# TX_LPF_Add_on.net
KiCad netlist of a schematic drawn in Altium Designer
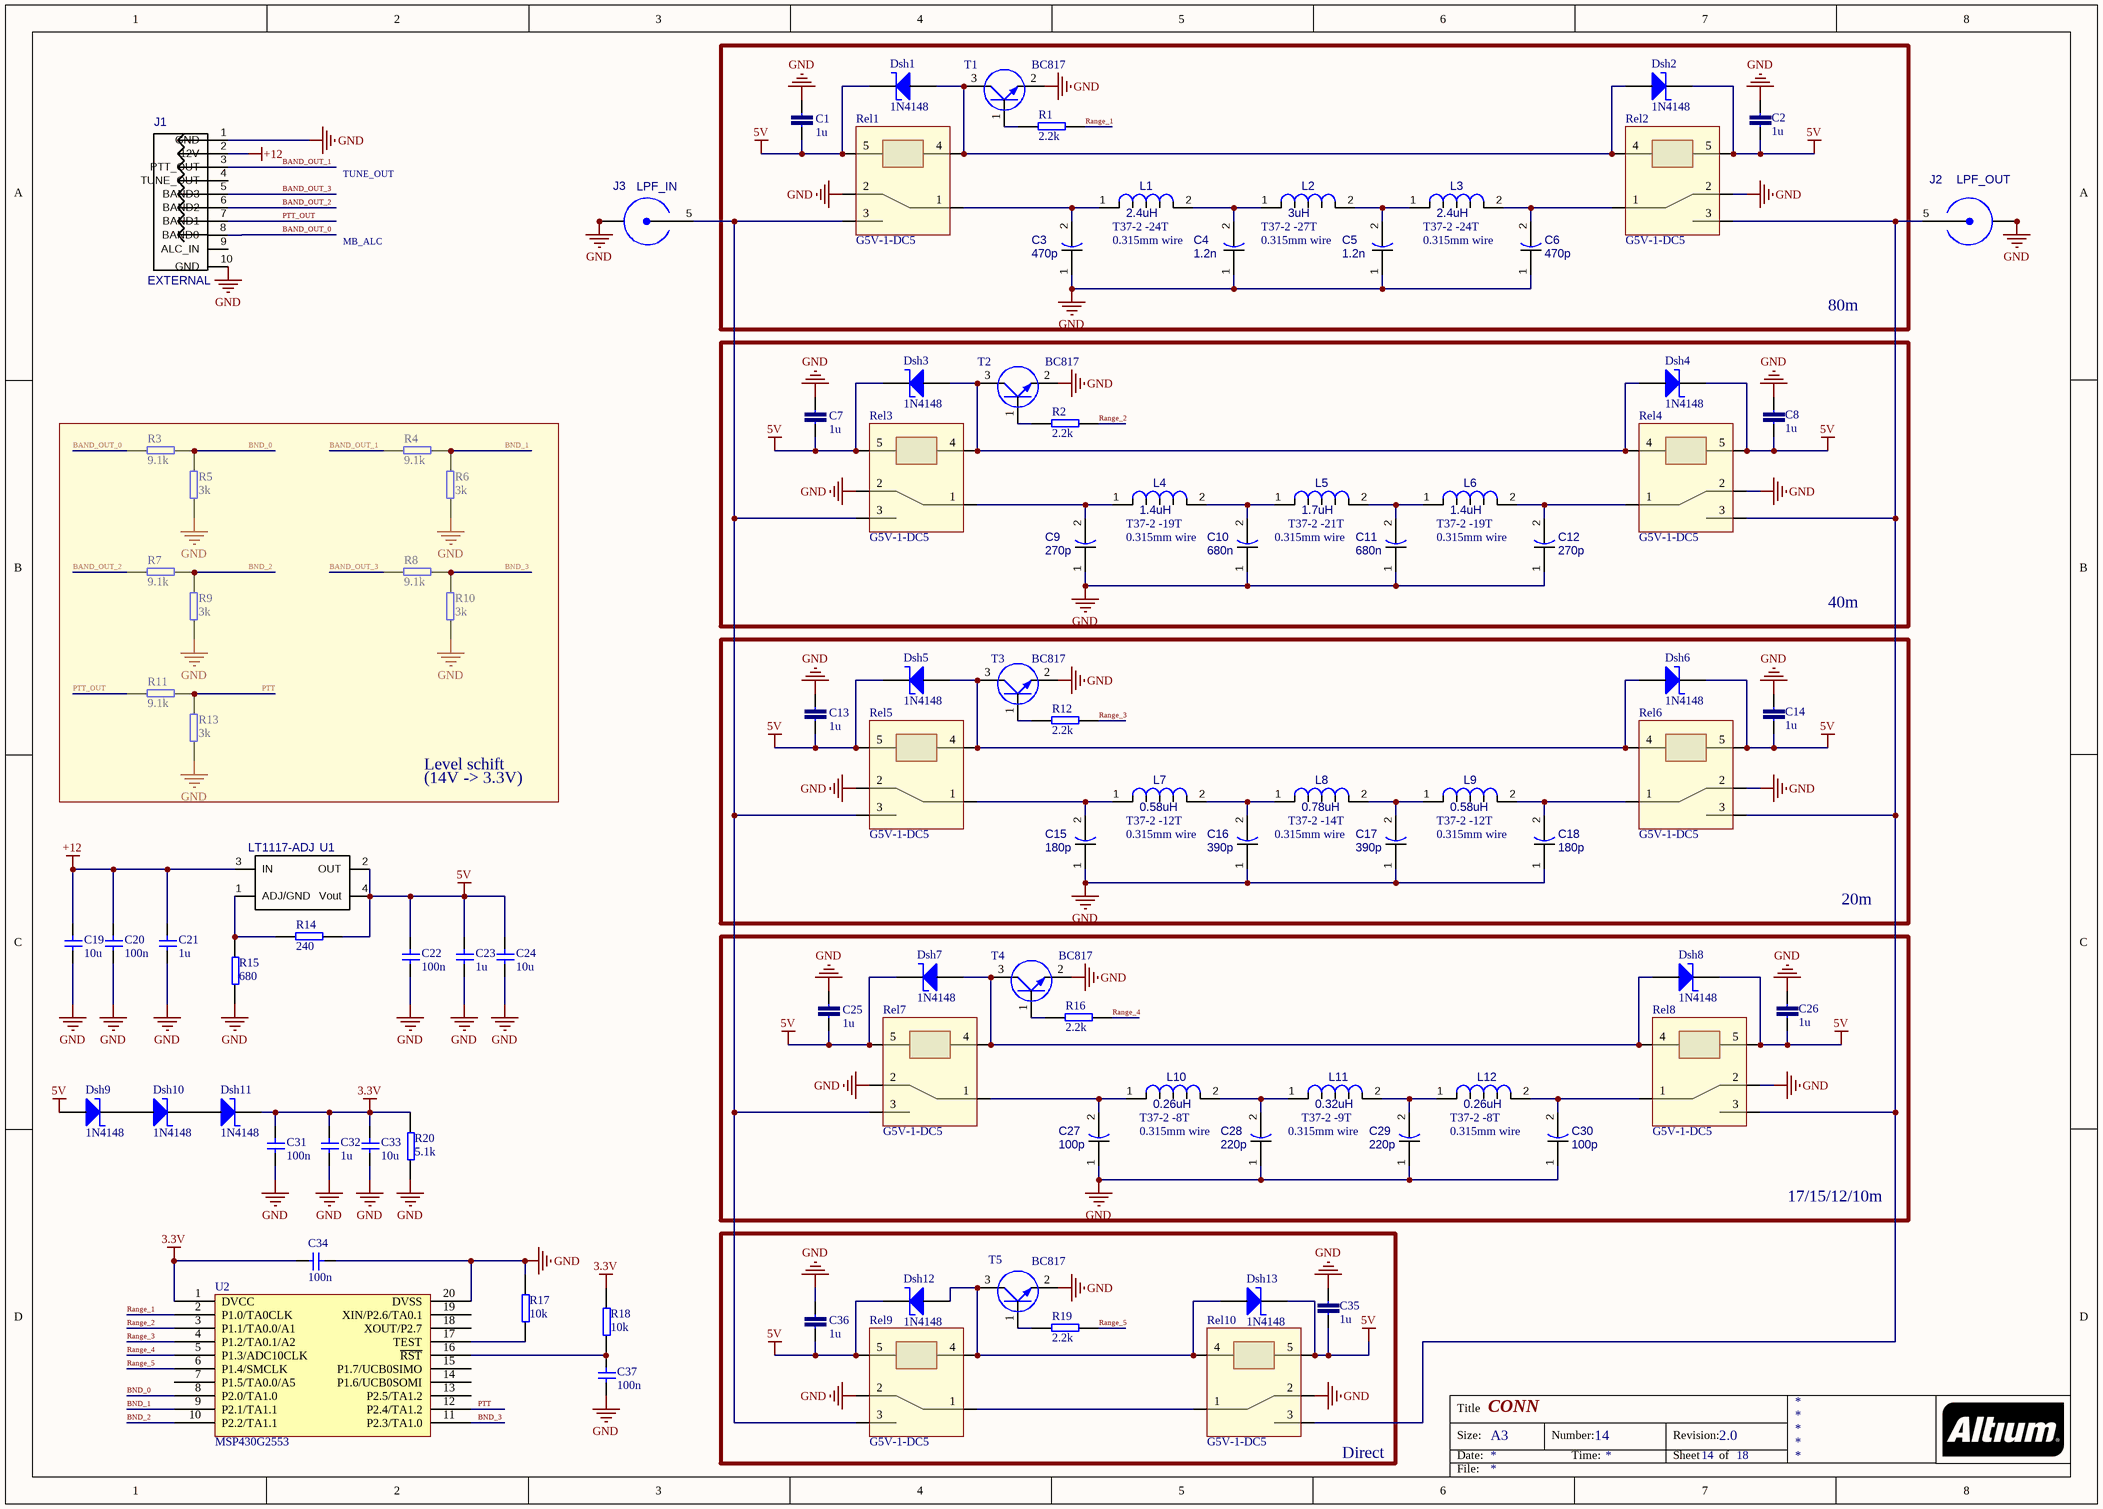
[diagram p0: TX_LPF_Add_on.SchDoc]

(export (version "E")
  (design (tool "Eeschema 10.0.6"))
  (components
    (comp (ref "C1")
      (value "1u")
      (footprint "0805S")
      (description "Capacitor")
      (libsource (lib "") (part "C-EUC0805_1"))
    )
    (comp (ref "C2")
      (value "1u")
      (footprint "0805S")
      (description "Capacitor")
      (libsource (lib "XXYZZB_1") (part "C-EUC0805"))
    )
    (comp (ref "C3")
      (value "470p")
      (footprint "CAP_5mm")
      (description "CAP_1206")
      (fields (field (name "Comment") "CAP_5mm"))
      (libsource (lib "RF-UNIT") (part "CAP_5mm"))
    )
    (comp (ref "C4")
      (value "1.2n")
      (footprint "CAP_5mm")
      (description "CAP_1206")
      (fields (field (name "Comment") "CAP_5mm"))
      (libsource (lib "RF-UNIT") (part "CAP_5mm"))
    )
    (comp (ref "C5")
      (value "1.2n")
      (footprint "CAP_5mm")
      (description "CAP_1206")
      (fields (field (name "Comment") "CAP_5mm"))
      (libsource (lib "RF-UNIT") (part "CAP_5mm"))
    )
    (comp (ref "C6")
      (value "470p")
      (footprint "CAP_5mm")
      (description "CAP_1206")
      (fields (field (name "Comment") "CAP_5mm"))
      (libsource (lib "RF-UNIT") (part "CAP_5mm"))
    )
    (comp (ref "C7")
      (value "1u")
      (footprint "0805S")
      (description "Capacitor")
      (libsource (lib "") (part "C-EUC0805_1"))
    )
    (comp (ref "C8")
      (value "1u")
      (footprint "0805S")
      (description "Capacitor")
      (libsource (lib "XXYZZB_1") (part "C-EUC0805"))
    )
    (comp (ref "C9")
      (value "270p")
      (footprint "CAP_5mm")
      (description "CAP_1206")
      (fields (field (name "Comment") "CAP_5mm"))
      (libsource (lib "RF-UNIT") (part "CAP_5mm"))
    )
    (comp (ref "C10")
      (value "680n")
      (footprint "CAP_5mm")
      (description "CAP_1206")
      (fields (field (name "Comment") "CAP_5mm"))
      (libsource (lib "RF-UNIT") (part "CAP_5mm"))
    )
    (comp (ref "C11")
      (value "680n")
      (footprint "CAP_5mm")
      (description "CAP_1206")
      (fields (field (name "Comment") "CAP_5mm"))
      (libsource (lib "RF-UNIT") (part "CAP_5mm"))
    )
    (comp (ref "C12")
      (value "270p")
      (footprint "CAP_5mm")
      (description "CAP_1206")
      (fields (field (name "Comment") "CAP_5mm"))
      (libsource (lib "RF-UNIT") (part "CAP_5mm"))
    )
    (comp (ref "C13")
      (value "1u")
      (footprint "0805S")
      (description "Capacitor")
      (libsource (lib "") (part "C-EUC0805_1"))
    )
    (comp (ref "C14")
      (value "1u")
      (footprint "0805S")
      (description "Capacitor")
      (libsource (lib "XXYZZB_1") (part "C-EUC0805"))
    )
    (comp (ref "C15")
      (value "180p")
      (footprint "CAP_5mm")
      (description "CAP_1206")
      (fields (field (name "Comment") "CAP_5mm"))
      (libsource (lib "RF-UNIT") (part "CAP_5mm"))
    )
    (comp (ref "C16")
      (value "390p")
      (footprint "CAP_5mm")
      (description "CAP_1206")
      (fields (field (name "Comment") "CAP_5mm"))
      (libsource (lib "RF-UNIT") (part "CAP_5mm"))
    )
    (comp (ref "C17")
      (value "390p")
      (footprint "CAP_5mm")
      (description "CAP_1206")
      (fields (field (name "Comment") "CAP_5mm"))
      (libsource (lib "RF-UNIT") (part "CAP_5mm"))
    )
    (comp (ref "C18")
      (value "180p")
      (footprint "CAP_5mm")
      (description "CAP_1206")
      (fields (field (name "Comment") "CAP_5mm"))
      (libsource (lib "RF-UNIT") (part "CAP_5mm"))
    )
    (comp (ref "C19")
      (value "10u")
      (footprint "CAP_1206")
      (description "Capacitor")
      (fields (field (name "Comment") "C0805"))
      (libsource (lib "Ivan DXP SCH LIB") (part "C0805"))
    )
    (comp (ref "C20")
      (value "100n")
      (footprint "0805S")
      (description "Capacitor")
      (fields (field (name "Comment") "C0805"))
      (libsource (lib "Ivan DXP SCH LIB") (part "C0805"))
    )
    (comp (ref "C21")
      (value "1u")
      (footprint "0805S")
      (description "Capacitor")
      (fields (field (name "Comment") "C0805"))
      (libsource (lib "Ivan DXP SCH LIB") (part "C0805"))
    )
    (comp (ref "C22")
      (value "100n")
      (footprint "0805S")
      (description "Capacitor")
      (fields (field (name "Comment") "C0805"))
      (libsource (lib "Ivan DXP SCH LIB") (part "C0805"))
    )
    (comp (ref "C23")
      (value "1u")
      (footprint "0805S")
      (description "Capacitor")
      (fields (field (name "Comment") "C0805"))
      (libsource (lib "Ivan DXP SCH LIB") (part "C0805"))
    )
    (comp (ref "C24")
      (value "10u")
      (footprint "CAP_1206")
      (description "Capacitor")
      (fields (field (name "Comment") "C0805"))
      (libsource (lib "Ivan DXP SCH LIB") (part "C0805"))
    )
    (comp (ref "C25")
      (value "1u")
      (footprint "0805S")
      (description "Capacitor")
      (libsource (lib "") (part "C-EUC0805_1"))
    )
    (comp (ref "C26")
      (value "1u")
      (footprint "0805S")
      (description "Capacitor")
      (libsource (lib "XXYZZB_1") (part "C-EUC0805"))
    )
    (comp (ref "C27")
      (value "100p")
      (footprint "CAP_5mm")
      (description "CAP_1206")
      (fields (field (name "Comment") "CAP_5mm"))
      (libsource (lib "RF-UNIT") (part "CAP_5mm"))
    )
    (comp (ref "C28")
      (value "220p")
      (footprint "CAP_5mm")
      (description "CAP_1206")
      (fields (field (name "Comment") "CAP_5mm"))
      (libsource (lib "RF-UNIT") (part "CAP_5mm"))
    )
    (comp (ref "C29")
      (value "220p")
      (footprint "CAP_5mm")
      (description "CAP_1206")
      (fields (field (name "Comment") "CAP_5mm"))
      (libsource (lib "RF-UNIT") (part "CAP_5mm"))
    )
    (comp (ref "C30")
      (value "100p")
      (footprint "CAP_5mm")
      (description "CAP_1206")
      (fields (field (name "Comment") "CAP_5mm"))
      (libsource (lib "RF-UNIT") (part "CAP_5mm"))
    )
    (comp (ref "C31")
      (value "100n")
      (footprint "0805S")
      (description "Capacitor")
      (fields (field (name "Comment") "C0805"))
      (libsource (lib "Ivan DXP SCH LIB") (part "C0805"))
    )
    (comp (ref "C32")
      (value "1u")
      (footprint "0805S")
      (description "Capacitor")
      (fields (field (name "Comment") "C0805"))
      (libsource (lib "Ivan DXP SCH LIB") (part "C0805"))
    )
    (comp (ref "C33")
      (value "10u")
      (footprint "CAP_1206")
      (description "Capacitor")
      (fields (field (name "Comment") "C0805"))
      (libsource (lib "Ivan DXP SCH LIB") (part "C0805"))
    )
    (comp (ref "C34")
      (value "100n")
      (footprint "0805S")
      (description "Capacitor")
      (fields (field (name "Comment") "C0805"))
      (libsource (lib "Ivan DXP SCH LIB") (part "C0805"))
    )
    (comp (ref "C35")
      (value "1u")
      (footprint "0805S")
      (description "Capacitor")
      (libsource (lib "XXYZZB_1") (part "C-EUC0805"))
    )
    (comp (ref "C36")
      (value "1u")
      (footprint "0805S")
      (description "Capacitor")
      (libsource (lib "") (part "C-EUC0805_1"))
    )
    (comp (ref "C37")
      (value "100n")
      (footprint "0805S")
      (description "Capacitor")
      (fields (field (name "Comment") "C0805"))
      (libsource (lib "Ivan DXP SCH LIB") (part "C0805"))
    )
    (comp (ref "Dsh1")
      (value "1N4148")
      (footprint "1N4148 (1005)")
      (description "Diode Shottky")
      (fields (field (name "Comment") "DIODE_Shottky_Micr.M"))
      (libsource (lib "Ivan DXP SCH LIB") (part "DIODE_Shottky_Micr.M"))
    )
    (comp (ref "Dsh2")
      (value "1N4148")
      (footprint "1N4148 (1005)")
      (description "Diode Shottky")
      (fields (field (name "Comment") "DIODE_Shottky_Micr.M"))
      (libsource (lib "Ivan DXP SCH LIB") (part "DIODE_Shottky_Micr.M"))
    )
    (comp (ref "Dsh3")
      (value "1N4148")
      (footprint "1N4148 (1005)")
      (description "Diode Shottky")
      (fields (field (name "Comment") "DIODE_Shottky_Micr.M"))
      (libsource (lib "Ivan DXP SCH LIB") (part "DIODE_Shottky_Micr.M"))
    )
    (comp (ref "Dsh4")
      (value "1N4148")
      (footprint "1N4148 (1005)")
      (description "Diode Shottky")
      (fields (field (name "Comment") "DIODE_Shottky_Micr.M"))
      (libsource (lib "Ivan DXP SCH LIB") (part "DIODE_Shottky_Micr.M"))
    )
    (comp (ref "Dsh5")
      (value "1N4148")
      (footprint "1N4148 (1005)")
      (description "Diode Shottky")
      (fields (field (name "Comment") "DIODE_Shottky_Micr.M"))
      (libsource (lib "Ivan DXP SCH LIB") (part "DIODE_Shottky_Micr.M"))
    )
    (comp (ref "Dsh6")
      (value "1N4148")
      (footprint "1N4148 (1005)")
      (description "Diode Shottky")
      (fields (field (name "Comment") "DIODE_Shottky_Micr.M"))
      (libsource (lib "Ivan DXP SCH LIB") (part "DIODE_Shottky_Micr.M"))
    )
    (comp (ref "Dsh7")
      (value "1N4148")
      (footprint "1N4148 (1005)")
      (description "Diode Shottky")
      (fields (field (name "Comment") "DIODE_Shottky_Micr.M"))
      (libsource (lib "Ivan DXP SCH LIB") (part "DIODE_Shottky_Micr.M"))
    )
    (comp (ref "Dsh8")
      (value "1N4148")
      (footprint "1N4148 (1005)")
      (description "Diode Shottky")
      (fields (field (name "Comment") "DIODE_Shottky_Micr.M"))
      (libsource (lib "Ivan DXP SCH LIB") (part "DIODE_Shottky_Micr.M"))
    )
    (comp (ref "Dsh9")
      (value "1N4148")
      (footprint "1N4148 (1005)")
      (description "Diode Shottky")
      (fields (field (name "Comment") "DIODE_Shottky_Micr.M"))
      (libsource (lib "Ivan DXP SCH LIB") (part "DIODE_Shottky_Micr.M"))
    )
    (comp (ref "Dsh10")
      (value "1N4148")
      (footprint "1N4148 (1005)")
      (description "Diode Shottky")
      (fields (field (name "Comment") "DIODE_Shottky_Micr.M"))
      (libsource (lib "Ivan DXP SCH LIB") (part "DIODE_Shottky_Micr.M"))
    )
    (comp (ref "Dsh11")
      (value "1N4148")
      (footprint "1N4148 (1005)")
      (description "Diode Shottky")
      (fields (field (name "Comment") "DIODE_Shottky_Micr.M"))
      (libsource (lib "Ivan DXP SCH LIB") (part "DIODE_Shottky_Micr.M"))
    )
    (comp (ref "Dsh12")
      (value "1N4148")
      (footprint "1N4148 (1005)")
      (description "Diode Shottky")
      (fields (field (name "Comment") "DIODE_Shottky_Micr.M"))
      (libsource (lib "Ivan DXP SCH LIB") (part "DIODE_Shottky_Micr.M"))
    )
    (comp (ref "Dsh13")
      (value "1N4148")
      (footprint "1N4148 (1005)")
      (description "Diode Shottky")
      (fields (field (name "Comment") "DIODE_Shottky_Micr.M"))
      (libsource (lib "Ivan DXP SCH LIB") (part "DIODE_Shottky_Micr.M"))
    )
    (comp (ref "J1")
      (value "EXTERNAL")
      (footprint "90131-0126")
      (description "2*5 PIN")
      (libsource (lib "RF-UNIT") (part "90131-0126"))
    )
    (comp (ref "J2")
      (value "LPF_OUT")
      (footprint "31-5431")
      (description "SMA")
      (fields (field (name "Comment") "Output"))
      (libsource (lib "RF-UNIT_1") (part "31-5431"))
    )
    (comp (ref "J3")
      (value "LPF_IN")
      (footprint "31-5431")
      (description "SMA")
      (fields (field (name "Comment") "Input"))
      (libsource (lib "RF-UNIT_1") (part "31-5431"))
    )
    (comp (ref "L1")
      (value "2.4uH")
      (footprint "IND_T37-2")
      (description "IND_T37-2")
      (libsource (lib "RF-UNIT") (part "IND_T37-2"))
    )
    (comp (ref "L2")
      (value "3uH")
      (footprint "IND_T37-2")
      (description "IND_T37-2")
      (libsource (lib "RF-UNIT") (part "IND_T37-2"))
    )
    (comp (ref "L3")
      (value "2.4uH")
      (footprint "IND_T37-2")
      (description "IND_T37-2")
      (libsource (lib "RF-UNIT") (part "IND_T37-2"))
    )
    (comp (ref "L4")
      (value "1.4uH")
      (footprint "IND_T37-2")
      (description "IND_T37-2")
      (libsource (lib "RF-UNIT") (part "IND_T37-2"))
    )
    (comp (ref "L5")
      (value "1.7uH")
      (footprint "IND_T37-2")
      (description "IND_T37-2")
      (libsource (lib "RF-UNIT") (part "IND_T37-2"))
    )
    (comp (ref "L6")
      (value "1.4uH")
      (footprint "IND_T37-2")
      (description "IND_T37-2")
      (libsource (lib "RF-UNIT") (part "IND_T37-2"))
    )
    (comp (ref "L7")
      (value "0.58uH")
      (footprint "IND_T37-2")
      (description "IND_T37-2")
      (libsource (lib "RF-UNIT") (part "IND_T37-2"))
    )
    (comp (ref "L8")
      (value "0.78uH")
      (footprint "IND_T37-2")
      (description "IND_T37-2")
      (libsource (lib "RF-UNIT") (part "IND_T37-2"))
    )
    (comp (ref "L9")
      (value "0.58uH")
      (footprint "IND_T37-2")
      (description "IND_T37-2")
      (libsource (lib "RF-UNIT") (part "IND_T37-2"))
    )
    (comp (ref "L10")
      (value "0.26uH")
      (footprint "IND_T37-2")
      (description "IND_T37-2")
      (libsource (lib "RF-UNIT") (part "IND_T37-2"))
    )
    (comp (ref "L11")
      (value "0.32uH")
      (footprint "IND_T37-2")
      (description "IND_T37-2")
      (libsource (lib "RF-UNIT") (part "IND_T37-2"))
    )
    (comp (ref "L12")
      (value "0.26uH")
      (footprint "IND_T37-2")
      (description "IND_T37-2")
      (libsource (lib "RF-UNIT") (part "IND_T37-2"))
    )
    (comp (ref "R1")
      (value "2.2k")
      (footprint "0805S")
      (description "Resistor")
      (libsource (lib "Ivan DXP SCH LIB") (part "R0805"))
    )
    (comp (ref "R2")
      (value "2.2k")
      (footprint "0805S")
      (description "Resistor")
      (libsource (lib "Ivan DXP SCH LIB") (part "R0805"))
    )
    (comp (ref "R3")
      (value "9.1k")
      (footprint "0805S")
      (description "Resistor")
      (fields (field (name "Comment") "R0805"))
      (libsource (lib "Ivan DXP SCH LIB") (part "R0805"))
    )
    (comp (ref "R4")
      (value "9.1k")
      (footprint "0805S")
      (description "Resistor")
      (fields (field (name "Comment") "R0805"))
      (libsource (lib "Ivan DXP SCH LIB") (part "R0805"))
    )
    (comp (ref "R5")
      (value "3k")
      (footprint "0805S")
      (description "Resistor")
      (fields (field (name "Comment") "R0805"))
      (libsource (lib "") (part "R0805_2"))
    )
    (comp (ref "R6")
      (value "3k")
      (footprint "0805S")
      (description "Resistor")
      (fields (field (name "Comment") "R0805"))
      (libsource (lib "") (part "R0805_2"))
    )
    (comp (ref "R7")
      (value "9.1k")
      (footprint "0805S")
      (description "Resistor")
      (fields (field (name "Comment") "R0805"))
      (libsource (lib "Ivan DXP SCH LIB") (part "R0805"))
    )
    (comp (ref "R8")
      (value "9.1k")
      (footprint "0805S")
      (description "Resistor")
      (fields (field (name "Comment") "R0805"))
      (libsource (lib "Ivan DXP SCH LIB") (part "R0805"))
    )
    (comp (ref "R9")
      (value "3k")
      (footprint "0805S")
      (description "Resistor")
      (fields (field (name "Comment") "R0805"))
      (libsource (lib "") (part "R0805_2"))
    )
    (comp (ref "R10")
      (value "3k")
      (footprint "0805S")
      (description "Resistor")
      (fields (field (name "Comment") "R0805"))
      (libsource (lib "") (part "R0805_2"))
    )
    (comp (ref "R11")
      (value "9.1k")
      (footprint "0805S")
      (description "Resistor")
      (fields (field (name "Comment") "R0805"))
      (libsource (lib "Ivan DXP SCH LIB") (part "R0805"))
    )
    (comp (ref "R12")
      (value "2.2k")
      (footprint "0805S")
      (description "Resistor")
      (libsource (lib "Ivan DXP SCH LIB") (part "R0805"))
    )
    (comp (ref "R13")
      (value "3k")
      (footprint "0805S")
      (description "Resistor")
      (fields (field (name "Comment") "R0805"))
      (libsource (lib "") (part "R0805_2"))
    )
    (comp (ref "R14")
      (value "240")
      (footprint "0805S")
      (description "Resistor")
      (fields (field (name "Comment") "R0805"))
      (libsource (lib "Ivan DXP SCH LIB") (part "R0805"))
    )
    (comp (ref "R15")
      (value "680")
      (footprint "0805S")
      (description "Resistor")
      (fields (field (name "Comment") "R0805"))
      (libsource (lib "") (part "R0805_1"))
    )
    (comp (ref "R16")
      (value "2.2k")
      (footprint "0805S")
      (description "Resistor")
      (libsource (lib "Ivan DXP SCH LIB") (part "R0805"))
    )
    (comp (ref "R17")
      (value "10k")
      (footprint "0805S")
      (description "Resistor")
      (fields (field (name "Comment") "R0805"))
      (libsource (lib "") (part "R0805_1"))
    )
    (comp (ref "R18")
      (value "10k")
      (footprint "0805S")
      (description "Resistor")
      (fields (field (name "Comment") "R0805"))
      (libsource (lib "") (part "R0805_1"))
    )
    (comp (ref "R19")
      (value "2.2k")
      (footprint "0805S")
      (description "Resistor")
      (libsource (lib "Ivan DXP SCH LIB") (part "R0805"))
    )
    (comp (ref "R20")
      (value "5.1k")
      (footprint "0805S")
      (description "Resistor")
      (fields (field (name "Comment") "R0805"))
      (libsource (lib "") (part "R0805_1"))
    )
    (comp (ref "Rel1")
      (value "G5V-1-DC5")
      (footprint "G5V-1")
      (libsource (lib "IC_Texas_Instruments_ADS805E_eec") (part "G5V-1-DC5"))
    )
    (comp (ref "Rel2") (value "G5V-1-DC5") (footprint "G5V-1") (libsource (lib "") (part "G5V-1-DC5_1")))
    (comp (ref "Rel3")
      (value "G5V-1-DC5")
      (footprint "G5V-1")
      (libsource (lib "IC_Texas_Instruments_ADS805E_eec") (part "G5V-1-DC5"))
    )
    (comp (ref "Rel4") (value "G5V-1-DC5") (footprint "G5V-1") (libsource (lib "") (part "G5V-1-DC5_1")))
    (comp (ref "Rel5")
      (value "G5V-1-DC5")
      (footprint "G5V-1")
      (libsource (lib "IC_Texas_Instruments_ADS805E_eec") (part "G5V-1-DC5"))
    )
    (comp (ref "Rel6") (value "G5V-1-DC5") (footprint "G5V-1") (libsource (lib "") (part "G5V-1-DC5_1")))
    (comp (ref "Rel7")
      (value "G5V-1-DC5")
      (footprint "G5V-1")
      (libsource (lib "IC_Texas_Instruments_ADS805E_eec") (part "G5V-1-DC5"))
    )
    (comp (ref "Rel8") (value "G5V-1-DC5") (footprint "G5V-1") (libsource (lib "") (part "G5V-1-DC5_1")))
    (comp (ref "Rel9")
      (value "G5V-1-DC5")
      (footprint "G5V-1")
      (libsource (lib "IC_Texas_Instruments_ADS805E_eec") (part "G5V-1-DC5"))
    )
    (comp (ref "Rel10") (value "G5V-1-DC5") (footprint "G5V-1") (libsource (lib "") (part "G5V-1-DC5_1")))
    (comp (ref "T1")
      (value "BC817")
      (footprint "SOT-23")
      (description "Bipol. Transistor")
      (fields (field (name "Comment") "NPN"))
      (libsource (lib "Ivan DXP SCH LIB") (part "NPN"))
    )
    (comp (ref "T2")
      (value "BC817")
      (footprint "SOT-23")
      (description "Bipol. Transistor")
      (fields (field (name "Comment") "NPN"))
      (libsource (lib "Ivan DXP SCH LIB") (part "NPN"))
    )
    (comp (ref "T3")
      (value "BC817")
      (footprint "SOT-23")
      (description "Bipol. Transistor")
      (fields (field (name "Comment") "NPN"))
      (libsource (lib "Ivan DXP SCH LIB") (part "NPN"))
    )
    (comp (ref "T4")
      (value "BC817")
      (footprint "SOT-23")
      (description "Bipol. Transistor")
      (fields (field (name "Comment") "NPN"))
      (libsource (lib "Ivan DXP SCH LIB") (part "NPN"))
    )
    (comp (ref "T5")
      (value "BC817")
      (footprint "SOT-23")
      (description "Bipol. Transistor")
      (fields (field (name "Comment") "NPN"))
      (libsource (lib "Ivan DXP SCH LIB") (part "NPN"))
    )
    (comp (ref "U1")
      (value "LT1117-ADJ")
      (footprint "LT1117IST-ADJ")
      (description "LT1117IST-ADJ")
      (libsource (lib "*") (part "LT1117IST-ADJ"))
    )
    (comp (ref "U2")
      (value "MSP430G2553")
      (footprint "DIP20M")
      (libsource (lib "Ivan DXP SCH LIB") (part "MSP430G2553"))
    )
  )
  (nets
    (net (code "1") (name "+12") (class "Default")
      (node (ref "C19") (pin "2") (pinfunction "2_2") (pintype "passive"))
      (node (ref "C20") (pin "2") (pinfunction "2_2") (pintype "passive"))
      (node (ref "C21") (pin "2") (pinfunction "2_2") (pintype "passive"))
      (node (ref "J1") (pin "2") (pinfunction "12V_2") (pintype "passive"))
      (node (ref "U1") (pin "3") (pinfunction "IN_3") (pintype "passive"))
    )
    (net (code "3") (name "/BAND_OUT_0") (class "Default")
      (node (ref "J1") (pin "8") (pinfunction "BAND0_8") (pintype "passive"))
      (node (ref "R3") (pin "1") (pinfunction "1_1") (pintype "passive"))
    )
    (net (code "4") (name "/BAND_OUT_1") (class "Default")
      (node (ref "J1") (pin "3") (pinfunction "PTT_OUT_3") (pintype "passive"))
      (node (ref "R4") (pin "1") (pinfunction "1_1") (pintype "passive"))
    )
    (net (code "5") (name "/BAND_OUT_2") (class "Default")
      (node (ref "J1") (pin "6") (pinfunction "BAND2_6") (pintype "passive"))
      (node (ref "R7") (pin "1") (pinfunction "1_1") (pintype "passive"))
    )
    (net (code "6") (name "/BAND_OUT_3") (class "Default")
      (node (ref "J1") (pin "5") (pinfunction "BAND3_5") (pintype "passive"))
      (node (ref "R8") (pin "1") (pinfunction "1_1") (pintype "passive"))
    )
    (net (code "7") (name "/BND_0") (class "Default")
      (node (ref "R3") (pin "2") (pinfunction "2_2") (pintype "passive"))
      (node (ref "R5") (pin "2") (pinfunction "2_2") (pintype "passive"))
      (node (ref "U2") (pin "8") (pinfunction "P2.0/TA1.0_8") (pintype "passive"))
    )
    (net (code "8") (name "/BND_1") (class "Default")
      (node (ref "R4") (pin "2") (pinfunction "2_2") (pintype "passive"))
      (node (ref "R6") (pin "2") (pinfunction "2_2") (pintype "passive"))
      (node (ref "U2") (pin "9") (pinfunction "P2.1/TA1.1_9") (pintype "passive"))
    )
    (net (code "9") (name "/BND_2") (class "Default")
      (node (ref "R7") (pin "2") (pinfunction "2_2") (pintype "passive"))
      (node (ref "R9") (pin "2") (pinfunction "2_2") (pintype "passive"))
      (node (ref "U2") (pin "10") (pinfunction "P2.2/TA1.1_10") (pintype "passive"))
    )
    (net (code "10") (name "/BND_3") (class "Default")
      (node (ref "R10") (pin "2") (pinfunction "2_2") (pintype "passive"))
      (node (ref "R8") (pin "2") (pinfunction "2_2") (pintype "passive"))
      (node (ref "U2") (pin "11") (pinfunction "P2.3/TA1.0_11") (pintype "passive"))
    )
    (net (code "11") (name "/PTT") (class "Default")
      (node (ref "R11") (pin "2") (pinfunction "2_2") (pintype "passive"))
      (node (ref "R13") (pin "2") (pinfunction "2_2") (pintype "passive"))
      (node (ref "U2") (pin "12") (pinfunction "P2.4/TA1.2_12") (pintype "passive"))
    )
    (net (code "12") (name "/PTT_OUT") (class "Default")
      (node (ref "J1") (pin "7") (pinfunction "BAND1_7") (pintype "passive"))
      (node (ref "R11") (pin "1") (pinfunction "1_1") (pintype "passive"))
    )
    (net (code "13") (name "/Range_1") (class "Default")
      (node (ref "R1") (pin "2") (pinfunction "2_2") (pintype "passive"))
      (node (ref "U2") (pin "2") (pinfunction "P1.0/TA0CLK_2") (pintype "passive"))
    )
    (net (code "14") (name "/Range_2") (class "Default")
      (node (ref "R2") (pin "2") (pinfunction "2_2") (pintype "passive"))
      (node (ref "U2") (pin "3") (pinfunction "P1.1/TA0.0/A1_3") (pintype "passive"))
    )
    (net (code "15") (name "/Range_3") (class "Default")
      (node (ref "R12") (pin "2") (pinfunction "2_2") (pintype "passive"))
      (node (ref "U2") (pin "4") (pinfunction "P1.2/TA0.1/A2_4") (pintype "passive"))
    )
    (net (code "16") (name "/Range_4") (class "Default")
      (node (ref "R16") (pin "2") (pinfunction "2_2") (pintype "passive"))
      (node (ref "U2") (pin "5") (pinfunction "P1.3/ADC10CLK_5") (pintype "passive"))
    )
    (net (code "17") (name "/Range_5") (class "Default")
      (node (ref "R19") (pin "2") (pinfunction "2_2") (pintype "passive"))
      (node (ref "U2") (pin "6") (pinfunction "P1.4/SMCLK_6") (pintype "passive"))
    )
    (net (code "18") (name "3.3V") (class "Default")
      (node (ref "C31") (pin "2") (pinfunction "2_2") (pintype "passive"))
      (node (ref "C32") (pin "2") (pinfunction "2_2") (pintype "passive"))
      (node (ref "C33") (pin "2") (pinfunction "2_2") (pintype "passive"))
      (node (ref "C34") (pin "1") (pinfunction "1_1") (pintype "passive"))
      (node (ref "Dsh11") (pin "K") (pinfunction "K_K") (pintype "passive"))
      (node (ref "R18") (pin "1") (pinfunction "1_1") (pintype "passive"))
      (node (ref "R20") (pin "1") (pinfunction "1_1") (pintype "passive"))
      (node (ref "U2") (pin "1") (pinfunction "DVCC_1") (pintype "passive"))
    )
    (net (code "19") (name "5V") (class "Default")
      (node (ref "C1") (pin "1") (pinfunction "1_1") (pintype "passive"))
      (node (ref "C13") (pin "1") (pinfunction "1_1") (pintype "passive"))
      (node (ref "C14") (pin "2") (pinfunction "2_2") (pintype "passive"))
      (node (ref "C2") (pin "2") (pinfunction "2_2") (pintype "passive"))
      (node (ref "C22") (pin "2") (pinfunction "2_2") (pintype "passive"))
      (node (ref "C23") (pin "2") (pinfunction "2_2") (pintype "passive"))
      (node (ref "C24") (pin "2") (pinfunction "2_2") (pintype "passive"))
      (node (ref "C25") (pin "1") (pinfunction "1_1") (pintype "passive"))
      (node (ref "C26") (pin "2") (pinfunction "2_2") (pintype "passive"))
      (node (ref "C35") (pin "2") (pinfunction "2_2") (pintype "passive"))
      (node (ref "C36") (pin "1") (pinfunction "1_1") (pintype "passive"))
      (node (ref "C7") (pin "1") (pinfunction "1_1") (pintype "passive"))
      (node (ref "C8") (pin "2") (pinfunction "2_2") (pintype "passive"))
      (node (ref "Dsh1") (pin "K") (pinfunction "K_K") (pintype "passive"))
      (node (ref "Dsh12") (pin "K") (pinfunction "K_K") (pintype "passive"))
      (node (ref "Dsh13") (pin "K") (pinfunction "K_K") (pintype "passive"))
      (node (ref "Dsh2") (pin "K") (pinfunction "K_K") (pintype "passive"))
      (node (ref "Dsh3") (pin "K") (pinfunction "K_K") (pintype "passive"))
      (node (ref "Dsh4") (pin "K") (pinfunction "K_K") (pintype "passive"))
      (node (ref "Dsh5") (pin "K") (pinfunction "K_K") (pintype "passive"))
      (node (ref "Dsh6") (pin "K") (pinfunction "K_K") (pintype "passive"))
      (node (ref "Dsh7") (pin "K") (pinfunction "K_K") (pintype "passive"))
      (node (ref "Dsh8") (pin "K") (pinfunction "K_K") (pintype "passive"))
      (node (ref "Dsh9") (pin "A") (pinfunction "A_A") (pintype "passive"))
      (node (ref "R14") (pin "2") (pinfunction "2_2") (pintype "passive"))
      (node (ref "Rel1") (pin "5") (pinfunction "5_5") (pintype "passive"))
      (node (ref "Rel10") (pin "5") (pinfunction "5_5") (pintype "passive"))
      (node (ref "Rel2") (pin "5") (pinfunction "5_5") (pintype "passive"))
      (node (ref "Rel3") (pin "5") (pinfunction "5_5") (pintype "passive"))
      (node (ref "Rel4") (pin "5") (pinfunction "5_5") (pintype "passive"))
      (node (ref "Rel5") (pin "5") (pinfunction "5_5") (pintype "passive"))
      (node (ref "Rel6") (pin "5") (pinfunction "5_5") (pintype "passive"))
      (node (ref "Rel7") (pin "5") (pinfunction "5_5") (pintype "passive"))
      (node (ref "Rel8") (pin "5") (pinfunction "5_5") (pintype "passive"))
      (node (ref "Rel9") (pin "5") (pinfunction "5_5") (pintype "passive"))
      (node (ref "U1") (pin "2") (pinfunction "OUT_2") (pintype "passive"))
      (node (ref "U1") (pin "4") (pinfunction "Vout_4") (pintype "passive"))
    )
    (net (code "20") (name "GND") (class "Default")
      (node (ref "C1") (pin "2") (pinfunction "2_2") (pintype "passive"))
      (node (ref "C10") (pin "1") (pinfunction "1_1") (pintype "passive"))
      (node (ref "C11") (pin "1") (pinfunction "1_1") (pintype "passive"))
      (node (ref "C12") (pin "1") (pinfunction "1_1") (pintype "passive"))
      (node (ref "C13") (pin "2") (pinfunction "2_2") (pintype "passive"))
      (node (ref "C14") (pin "1") (pinfunction "1_1") (pintype "passive"))
      (node (ref "C15") (pin "1") (pinfunction "1_1") (pintype "passive"))
      (node (ref "C16") (pin "1") (pinfunction "1_1") (pintype "passive"))
      (node (ref "C17") (pin "1") (pinfunction "1_1") (pintype "passive"))
      (node (ref "C18") (pin "1") (pinfunction "1_1") (pintype "passive"))
      (node (ref "C19") (pin "1") (pinfunction "1_1") (pintype "passive"))
      (node (ref "C2") (pin "1") (pinfunction "1_1") (pintype "passive"))
      (node (ref "C20") (pin "1") (pinfunction "1_1") (pintype "passive"))
      (node (ref "C21") (pin "1") (pinfunction "1_1") (pintype "passive"))
      (node (ref "C22") (pin "1") (pinfunction "1_1") (pintype "passive"))
      (node (ref "C23") (pin "1") (pinfunction "1_1") (pintype "passive"))
      (node (ref "C24") (pin "1") (pinfunction "1_1") (pintype "passive"))
      (node (ref "C25") (pin "2") (pinfunction "2_2") (pintype "passive"))
      (node (ref "C26") (pin "1") (pinfunction "1_1") (pintype "passive"))
      (node (ref "C27") (pin "1") (pinfunction "1_1") (pintype "passive"))
      (node (ref "C28") (pin "1") (pinfunction "1_1") (pintype "passive"))
      (node (ref "C29") (pin "1") (pinfunction "1_1") (pintype "passive"))
      (node (ref "C3") (pin "1") (pinfunction "1_1") (pintype "passive"))
      (node (ref "C30") (pin "1") (pinfunction "1_1") (pintype "passive"))
      (node (ref "C31") (pin "1") (pinfunction "1_1") (pintype "passive"))
      (node (ref "C32") (pin "1") (pinfunction "1_1") (pintype "passive"))
      (node (ref "C33") (pin "1") (pinfunction "1_1") (pintype "passive"))
      (node (ref "C34") (pin "2") (pinfunction "2_2") (pintype "passive"))
      (node (ref "C35") (pin "1") (pinfunction "1_1") (pintype "passive"))
      (node (ref "C36") (pin "2") (pinfunction "2_2") (pintype "passive"))
      (node (ref "C37") (pin "1") (pinfunction "1_1") (pintype "passive"))
      (node (ref "C4") (pin "1") (pinfunction "1_1") (pintype "passive"))
      (node (ref "C5") (pin "1") (pinfunction "1_1") (pintype "passive"))
      (node (ref "C6") (pin "1") (pinfunction "1_1") (pintype "passive"))
      (node (ref "C7") (pin "2") (pinfunction "2_2") (pintype "passive"))
      (node (ref "C8") (pin "1") (pinfunction "1_1") (pintype "passive"))
      (node (ref "C9") (pin "1") (pinfunction "1_1") (pintype "passive"))
      (node (ref "J1") (pin "1") (pinfunction "GND_1") (pintype "passive"))
      (node (ref "J1") (pin "10") (pinfunction "GND_10") (pintype "passive"))
      (node (ref "J2") (pin "1") (pinfunction "GND_1") (pintype "passive"))
      (node (ref "J2") (pin "2") (pinfunction "GND_2") (pintype "passive"))
      (node (ref "J2") (pin "3") (pinfunction "GND_3") (pintype "passive"))
      (node (ref "J2") (pin "4") (pinfunction "GND_4") (pintype "passive"))
      (node (ref "J3") (pin "1") (pinfunction "GND_1") (pintype "passive"))
      (node (ref "J3") (pin "2") (pinfunction "GND_2") (pintype "passive"))
      (node (ref "J3") (pin "3") (pinfunction "GND_3") (pintype "passive"))
      (node (ref "J3") (pin "4") (pinfunction "GND_4") (pintype "passive"))
      (node (ref "R10") (pin "1") (pinfunction "1_1") (pintype "passive"))
      (node (ref "R13") (pin "1") (pinfunction "1_1") (pintype "passive"))
      (node (ref "R15") (pin "2") (pinfunction "2_2") (pintype "passive"))
      (node (ref "R17") (pin "1") (pinfunction "1_1") (pintype "passive"))
      (node (ref "R20") (pin "2") (pinfunction "2_2") (pintype "passive"))
      (node (ref "R5") (pin "1") (pinfunction "1_1") (pintype "passive"))
      (node (ref "R6") (pin "1") (pinfunction "1_1") (pintype "passive"))
      (node (ref "R9") (pin "1") (pinfunction "1_1") (pintype "passive"))
      (node (ref "Rel1") (pin "2") (pinfunction "2_2") (pintype "passive"))
      (node (ref "Rel10") (pin "2") (pinfunction "2_2") (pintype "passive"))
      (node (ref "Rel2") (pin "2") (pinfunction "2_2") (pintype "passive"))
      (node (ref "Rel3") (pin "2") (pinfunction "2_2") (pintype "passive"))
      (node (ref "Rel4") (pin "2") (pinfunction "2_2") (pintype "passive"))
      (node (ref "Rel5") (pin "2") (pinfunction "2_2") (pintype "passive"))
      (node (ref "Rel6") (pin "2") (pinfunction "2_2") (pintype "passive"))
      (node (ref "Rel7") (pin "2") (pinfunction "2_2") (pintype "passive"))
      (node (ref "Rel8") (pin "2") (pinfunction "2_2") (pintype "passive"))
      (node (ref "Rel9") (pin "2") (pinfunction "2_2") (pintype "passive"))
      (node (ref "T1") (pin "2") (pinfunction "2_2") (pintype "passive"))
      (node (ref "T2") (pin "2") (pinfunction "2_2") (pintype "passive"))
      (node (ref "T3") (pin "2") (pinfunction "2_2") (pintype "passive"))
      (node (ref "T4") (pin "2") (pinfunction "2_2") (pintype "passive"))
      (node (ref "T5") (pin "2") (pinfunction "2_2") (pintype "passive"))
      (node (ref "U2") (pin "20") (pinfunction "DVSS_20") (pintype "passive"))
    )
    (net (code "21") (name "Net-(C3-Pad2)") (class "Default")
      (node (ref "C3") (pin "2") (pinfunction "2_2") (pintype "passive"))
      (node (ref "L1") (pin "1") (pinfunction "1_1") (pintype "passive"))
      (node (ref "Rel1") (pin "1") (pinfunction "1_1") (pintype "passive"))
    )
    (net (code "22") (name "Net-(C4-Pad2)") (class "Default")
      (node (ref "C4") (pin "2") (pinfunction "2_2") (pintype "passive"))
      (node (ref "L1") (pin "2") (pinfunction "2_2") (pintype "passive"))
      (node (ref "L2") (pin "1") (pinfunction "1_1") (pintype "passive"))
    )
    (net (code "23") (name "Net-(C5-Pad2)") (class "Default")
      (node (ref "C5") (pin "2") (pinfunction "2_2") (pintype "passive"))
      (node (ref "L2") (pin "2") (pinfunction "2_2") (pintype "passive"))
      (node (ref "L3") (pin "1") (pinfunction "1_1") (pintype "passive"))
    )
    (net (code "24") (name "Net-(C6-Pad2)") (class "Default")
      (node (ref "C6") (pin "2") (pinfunction "2_2") (pintype "passive"))
      (node (ref "L3") (pin "2") (pinfunction "2_2") (pintype "passive"))
      (node (ref "Rel2") (pin "1") (pinfunction "1_1") (pintype "passive"))
    )
    (net (code "25") (name "Net-(C9-Pad2)") (class "Default")
      (node (ref "C9") (pin "2") (pinfunction "2_2") (pintype "passive"))
      (node (ref "L4") (pin "1") (pinfunction "1_1") (pintype "passive"))
      (node (ref "Rel3") (pin "1") (pinfunction "1_1") (pintype "passive"))
    )
    (net (code "26") (name "Net-(C10-Pad2)") (class "Default")
      (node (ref "C10") (pin "2") (pinfunction "2_2") (pintype "passive"))
      (node (ref "L4") (pin "2") (pinfunction "2_2") (pintype "passive"))
      (node (ref "L5") (pin "1") (pinfunction "1_1") (pintype "passive"))
    )
    (net (code "27") (name "Net-(C11-Pad2)") (class "Default")
      (node (ref "C11") (pin "2") (pinfunction "2_2") (pintype "passive"))
      (node (ref "L5") (pin "2") (pinfunction "2_2") (pintype "passive"))
      (node (ref "L6") (pin "1") (pinfunction "1_1") (pintype "passive"))
    )
    (net (code "28") (name "Net-(C12-Pad2)") (class "Default")
      (node (ref "C12") (pin "2") (pinfunction "2_2") (pintype "passive"))
      (node (ref "L6") (pin "2") (pinfunction "2_2") (pintype "passive"))
      (node (ref "Rel4") (pin "1") (pinfunction "1_1") (pintype "passive"))
    )
    (net (code "29") (name "Net-(C15-Pad2)") (class "Default")
      (node (ref "C15") (pin "2") (pinfunction "2_2") (pintype "passive"))
      (node (ref "L7") (pin "1") (pinfunction "1_1") (pintype "passive"))
      (node (ref "Rel5") (pin "1") (pinfunction "1_1") (pintype "passive"))
    )
    (net (code "30") (name "Net-(C16-Pad2)") (class "Default")
      (node (ref "C16") (pin "2") (pinfunction "2_2") (pintype "passive"))
      (node (ref "L7") (pin "2") (pinfunction "2_2") (pintype "passive"))
      (node (ref "L8") (pin "1") (pinfunction "1_1") (pintype "passive"))
    )
    (net (code "31") (name "Net-(C17-Pad2)") (class "Default")
      (node (ref "C17") (pin "2") (pinfunction "2_2") (pintype "passive"))
      (node (ref "L8") (pin "2") (pinfunction "2_2") (pintype "passive"))
      (node (ref "L9") (pin "1") (pinfunction "1_1") (pintype "passive"))
    )
    (net (code "32") (name "Net-(C18-Pad2)") (class "Default")
      (node (ref "C18") (pin "2") (pinfunction "2_2") (pintype "passive"))
      (node (ref "L9") (pin "2") (pinfunction "2_2") (pintype "passive"))
      (node (ref "Rel6") (pin "1") (pinfunction "1_1") (pintype "passive"))
    )
    (net (code "33") (name "Net-(C27-Pad2)") (class "Default")
      (node (ref "C27") (pin "2") (pinfunction "2_2") (pintype "passive"))
      (node (ref "L10") (pin "1") (pinfunction "1_1") (pintype "passive"))
      (node (ref "Rel7") (pin "1") (pinfunction "1_1") (pintype "passive"))
    )
    (net (code "34") (name "Net-(C28-Pad2)") (class "Default")
      (node (ref "C28") (pin "2") (pinfunction "2_2") (pintype "passive"))
      (node (ref "L10") (pin "2") (pinfunction "2_2") (pintype "passive"))
      (node (ref "L11") (pin "1") (pinfunction "1_1") (pintype "passive"))
    )
    (net (code "35") (name "Net-(C29-Pad2)") (class "Default")
      (node (ref "C29") (pin "2") (pinfunction "2_2") (pintype "passive"))
      (node (ref "L11") (pin "2") (pinfunction "2_2") (pintype "passive"))
      (node (ref "L12") (pin "1") (pinfunction "1_1") (pintype "passive"))
    )
    (net (code "36") (name "Net-(C30-Pad2)") (class "Default")
      (node (ref "C30") (pin "2") (pinfunction "2_2") (pintype "passive"))
      (node (ref "L12") (pin "2") (pinfunction "2_2") (pintype "passive"))
      (node (ref "Rel8") (pin "1") (pinfunction "1_1") (pintype "passive"))
    )
    (net (code "37") (name "Net-(Dsh1-PadA)") (class "Default")
      (node (ref "Dsh1") (pin "A") (pinfunction "A_A") (pintype "passive"))
      (node (ref "Dsh2") (pin "A") (pinfunction "A_A") (pintype "passive"))
      (node (ref "Rel1") (pin "4") (pinfunction "4_4") (pintype "passive"))
      (node (ref "Rel2") (pin "4") (pinfunction "4_4") (pintype "passive"))
      (node (ref "T1") (pin "3") (pinfunction "3_3") (pintype "passive"))
    )
    (net (code "38") (name "Net-(Dsh3-PadA)") (class "Default")
      (node (ref "Dsh3") (pin "A") (pinfunction "A_A") (pintype "passive"))
      (node (ref "Dsh4") (pin "A") (pinfunction "A_A") (pintype "passive"))
      (node (ref "Rel3") (pin "4") (pinfunction "4_4") (pintype "passive"))
      (node (ref "Rel4") (pin "4") (pinfunction "4_4") (pintype "passive"))
      (node (ref "T2") (pin "3") (pinfunction "3_3") (pintype "passive"))
    )
    (net (code "39") (name "Net-(Dsh5-PadA)") (class "Default")
      (node (ref "Dsh5") (pin "A") (pinfunction "A_A") (pintype "passive"))
      (node (ref "Dsh6") (pin "A") (pinfunction "A_A") (pintype "passive"))
      (node (ref "Rel5") (pin "4") (pinfunction "4_4") (pintype "passive"))
      (node (ref "Rel6") (pin "4") (pinfunction "4_4") (pintype "passive"))
      (node (ref "T3") (pin "3") (pinfunction "3_3") (pintype "passive"))
    )
    (net (code "40") (name "Net-(Dsh7-PadA)") (class "Default")
      (node (ref "Dsh7") (pin "A") (pinfunction "A_A") (pintype "passive"))
      (node (ref "Dsh8") (pin "A") (pinfunction "A_A") (pintype "passive"))
      (node (ref "Rel7") (pin "4") (pinfunction "4_4") (pintype "passive"))
      (node (ref "Rel8") (pin "4") (pinfunction "4_4") (pintype "passive"))
      (node (ref "T4") (pin "3") (pinfunction "3_3") (pintype "passive"))
    )
    (net (code "41") (name "Net-(Dsh10-PadA)") (class "Default")
      (node (ref "Dsh10") (pin "A") (pinfunction "A_A") (pintype "passive"))
      (node (ref "Dsh9") (pin "K") (pinfunction "K_K") (pintype "passive"))
    )
    (net (code "42") (name "Net-(Dsh10-PadK)") (class "Default")
      (node (ref "Dsh10") (pin "K") (pinfunction "K_K") (pintype "passive"))
      (node (ref "Dsh11") (pin "A") (pinfunction "A_A") (pintype "passive"))
    )
    (net (code "43") (name "Net-(Dsh12-PadA)") (class "Default")
      (node (ref "Dsh12") (pin "A") (pinfunction "A_A") (pintype "passive"))
      (node (ref "Dsh13") (pin "A") (pinfunction "A_A") (pintype "passive"))
      (node (ref "Rel10") (pin "4") (pinfunction "4_4") (pintype "passive"))
      (node (ref "Rel9") (pin "4") (pinfunction "4_4") (pintype "passive"))
      (node (ref "T5") (pin "3") (pinfunction "3_3") (pintype "passive"))
    )
    (net (code "44") (name "Net-(J2-CON)") (class "Default")
      (node (ref "J2") (pin "5") (pinfunction "CON_5") (pintype "passive"))
      (node (ref "Rel10") (pin "3") (pinfunction "3_3") (pintype "passive"))
      (node (ref "Rel2") (pin "3") (pinfunction "3_3") (pintype "passive"))
      (node (ref "Rel4") (pin "3") (pinfunction "3_3") (pintype "passive"))
      (node (ref "Rel6") (pin "3") (pinfunction "3_3") (pintype "passive"))
      (node (ref "Rel8") (pin "3") (pinfunction "3_3") (pintype "passive"))
    )
    (net (code "45") (name "Net-(J3-CON)") (class "Default")
      (node (ref "J3") (pin "5") (pinfunction "CON_5") (pintype "passive"))
      (node (ref "Rel1") (pin "3") (pinfunction "3_3") (pintype "passive"))
      (node (ref "Rel3") (pin "3") (pinfunction "3_3") (pintype "passive"))
      (node (ref "Rel5") (pin "3") (pinfunction "3_3") (pintype "passive"))
      (node (ref "Rel7") (pin "3") (pinfunction "3_3") (pintype "passive"))
      (node (ref "Rel9") (pin "3") (pinfunction "3_3") (pintype "passive"))
    )
    (net (code "46") (name "Net-(R1-Pad1)") (class "Default")
      (node (ref "R1") (pin "1") (pinfunction "1_1") (pintype "passive"))
      (node (ref "T1") (pin "1") (pinfunction "1_1") (pintype "passive"))
    )
    (net (code "47") (name "Net-(R2-Pad1)") (class "Default")
      (node (ref "R2") (pin "1") (pinfunction "1_1") (pintype "passive"))
      (node (ref "T2") (pin "1") (pinfunction "1_1") (pintype "passive"))
    )
    (net (code "48") (name "Net-(R12-Pad1)") (class "Default")
      (node (ref "R12") (pin "1") (pinfunction "1_1") (pintype "passive"))
      (node (ref "T3") (pin "1") (pinfunction "1_1") (pintype "passive"))
    )
    (net (code "49") (name "Net-(R16-Pad1)") (class "Default")
      (node (ref "R16") (pin "1") (pinfunction "1_1") (pintype "passive"))
      (node (ref "T4") (pin "1") (pinfunction "1_1") (pintype "passive"))
    )
    (net (code "50") (name "Net-(R19-Pad1)") (class "Default")
      (node (ref "R19") (pin "1") (pinfunction "1_1") (pintype "passive"))
      (node (ref "T5") (pin "1") (pinfunction "1_1") (pintype "passive"))
    )
    (net (code "51") (name "Net-(Rel10-Pad1)") (class "Default")
      (node (ref "Rel10") (pin "1") (pinfunction "1_1") (pintype "passive"))
      (node (ref "Rel9") (pin "1") (pinfunction "1_1") (pintype "passive"))
    )
    (net (code "52") (name "Net-(U1-ADJ{slash}GND)") (class "Default")
      (node (ref "R14") (pin "1") (pinfunction "1_1") (pintype "passive"))
      (node (ref "R15") (pin "1") (pinfunction "1_1") (pintype "passive"))
      (node (ref "U1") (pin "1") (pinfunction "ADJ/GND_1") (pintype "passive"))
    )
    (net (code "53") (name "Net-(U2-TEST)") (class "Default")
      (node (ref "R17") (pin "2") (pinfunction "2_2") (pintype "passive"))
      (node (ref "U2") (pin "17") (pinfunction "TEST_17") (pintype "passive"))
    )
    (net (code "54") (name "Net-(U2-~{RST})") (class "Default")
      (node (ref "C37") (pin "2") (pinfunction "2_2") (pintype "passive"))
      (node (ref "R18") (pin "2") (pinfunction "2_2") (pintype "passive"))
      (node (ref "U2") (pin "16") (pinfunction "~{RST}_16") (pintype "passive"))
    )
    (net (code "55") (name "unconnected-(J1-ALC_IN-Pad9)") (class "Default")
      (node (ref "J1") (pin "9") (pinfunction "ALC_IN_9") (pintype "passive"))
    )
    (net (code "56") (name "unconnected-(J1-TUNE_OUT-Pad4)") (class "Default")
      (node (ref "J1") (pin "4") (pinfunction "TUNE_OUT_4") (pintype "passive"))
    )
    (net (code "57") (name "unconnected-(U2-P1.5{slash}TA0.0{slash}A5-Pad7)") (class "Default")
      (node (ref "U2") (pin "7") (pinfunction "P1.5/TA0.0/A5_7") (pintype "passive"))
    )
    (net (code "58") (name "unconnected-(U2-P1.6{slash}UCB0SOMI-Pad14)") (class "Default")
      (node (ref "U2") (pin "14") (pinfunction "P1.6/UCB0SOMI_14") (pintype "passive"))
    )
    (net (code "59") (name "unconnected-(U2-P1.7{slash}UCB0SIMO-Pad15)") (class "Default")
      (node (ref "U2") (pin "15") (pinfunction "P1.7/UCB0SIMO_15") (pintype "passive"))
    )
    (net (code "60") (name "unconnected-(U2-P2.5{slash}TA1.2-Pad13)") (class "Default")
      (node (ref "U2") (pin "13") (pinfunction "P2.5/TA1.2_13") (pintype "passive"))
    )
    (net (code "61") (name "unconnected-(U2-XIN{slash}P2.6{slash}TA0.1-Pad19)") (class "Default")
      (node (ref "U2") (pin "19") (pinfunction "XIN/P2.6/TA0.1_19") (pintype "passive"))
    )
    (net (code "62") (name "unconnected-(U2-XOUT{slash}P2.7-Pad18)") (class "Default")
      (node (ref "U2") (pin "18") (pinfunction "XOUT/P2.7_18") (pintype "passive"))
    )
  )
)
